# SCH_BSPD_Main.net
KiCad netlist of a schematic drawn in Altium Designer
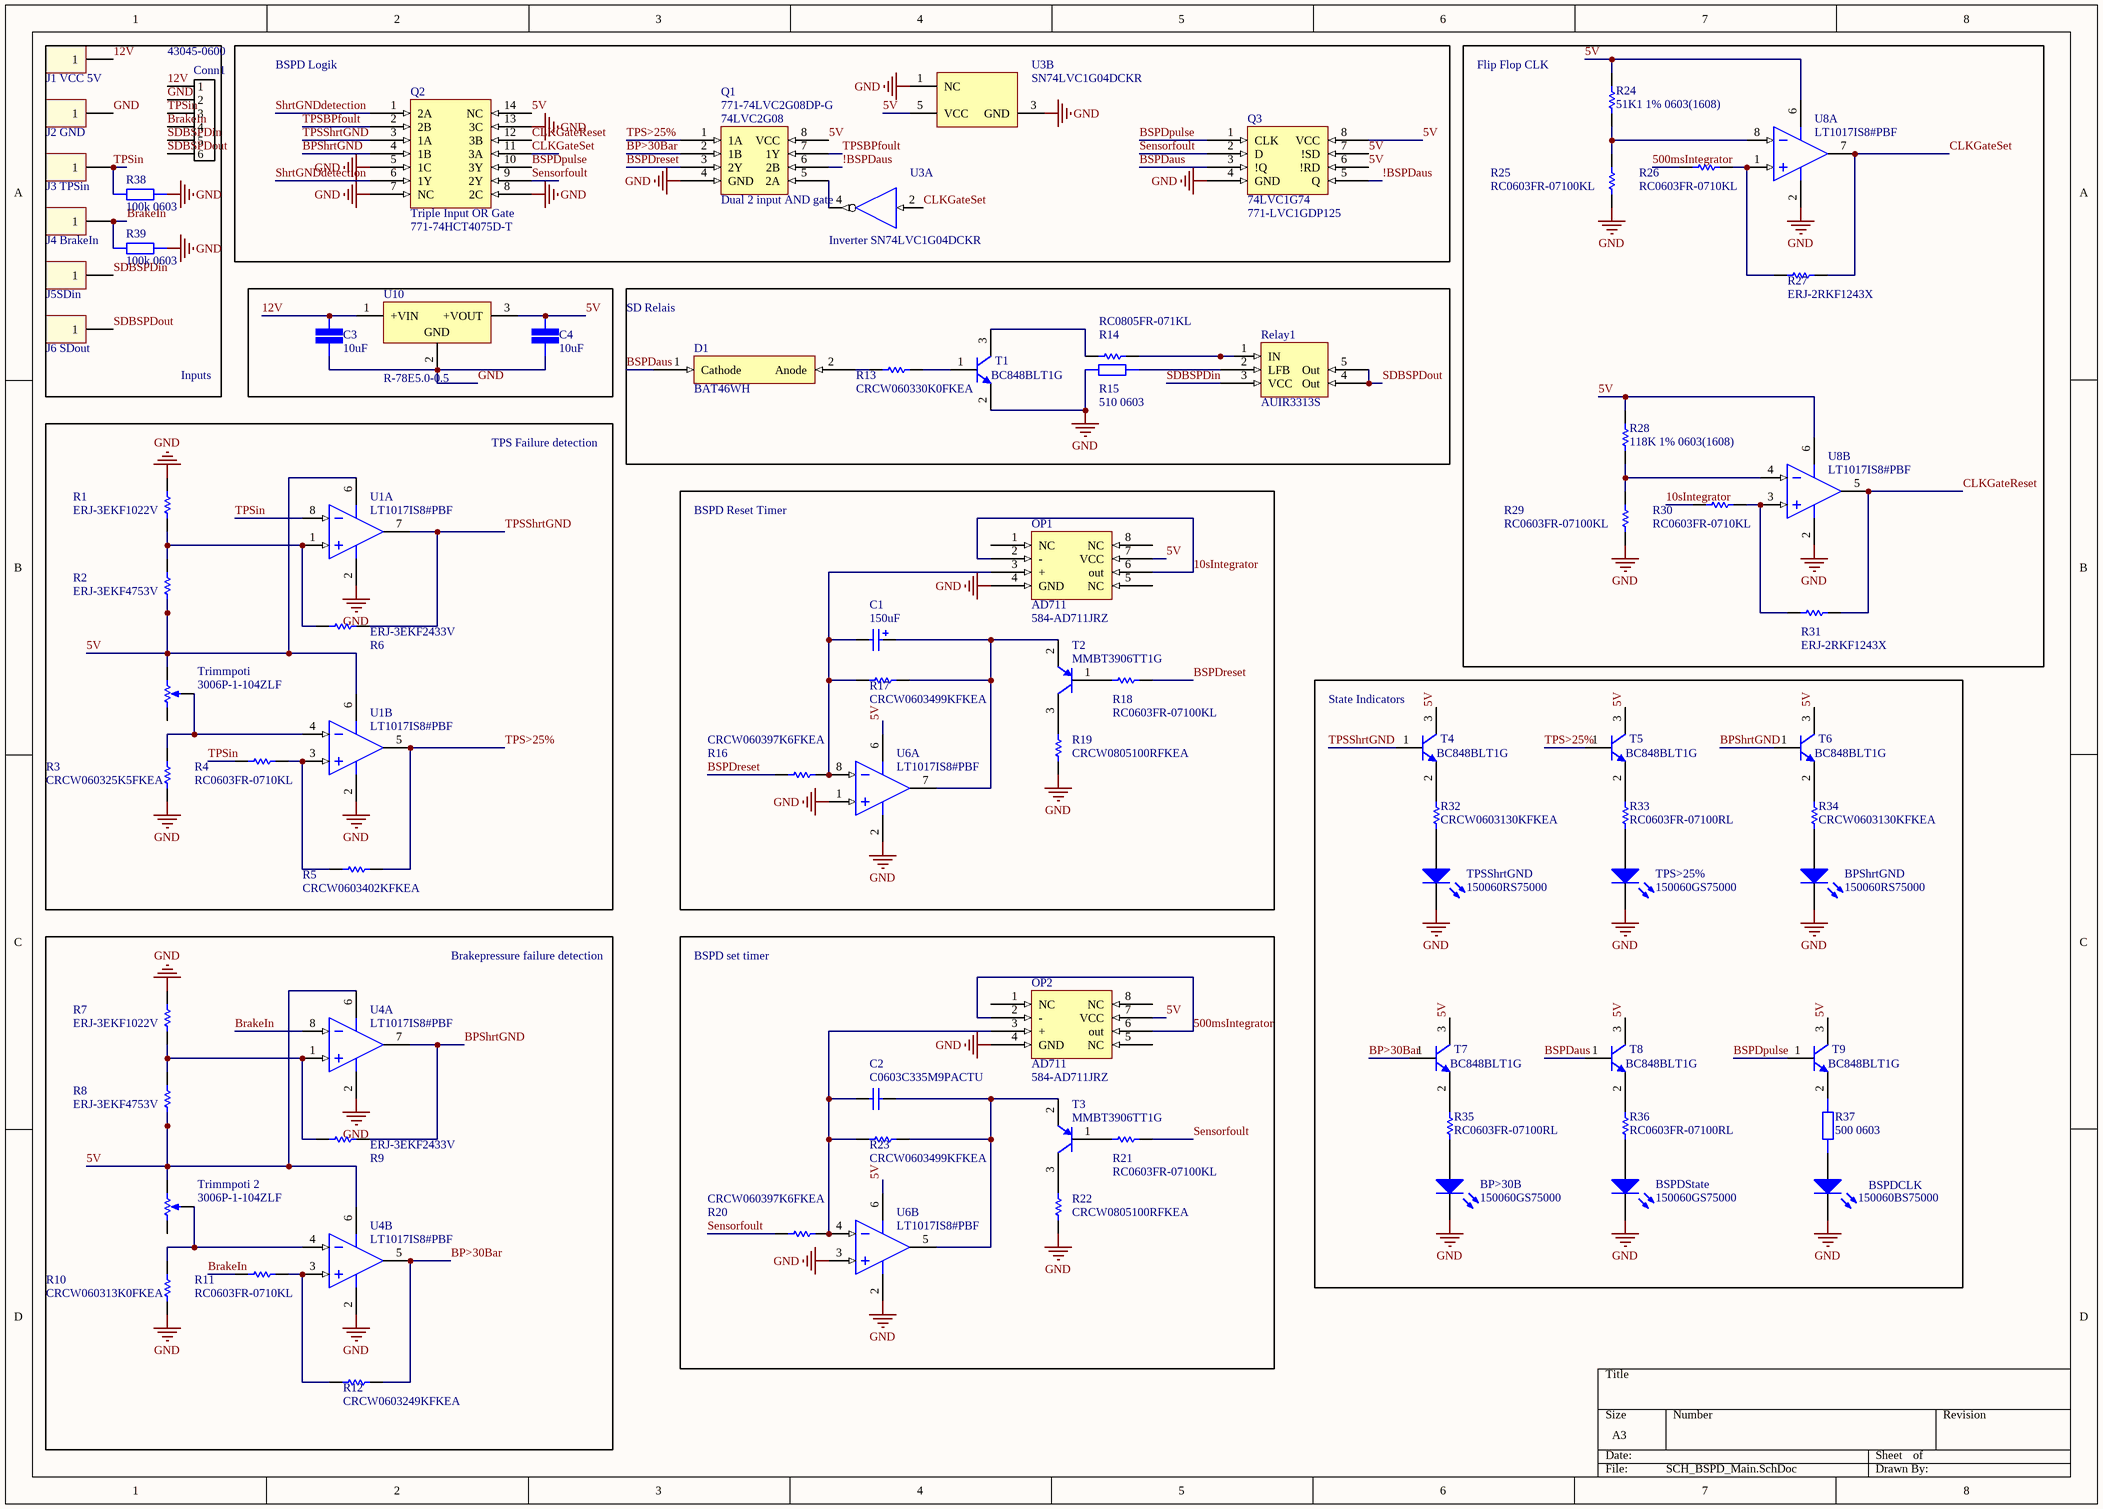
[diagram p0: SCH_BSPD_Main.SchDoc]

(export (version "E")
  (design (tool "Eeschema 10.0.6"))
  (components
    (comp (ref "BP>30B")
      (value "150060GS75000")
      (footprint "0603_A")
      (description "SMD mono-color Chip LED, WL-SMCW, Green")
      (fields (field (name "MANUFACTURER") "Wuerth Elektronik"))
      (libsource (lib "Altium Content Vault") (part "WE-LED_K1A2-2"))
    )
    (comp (ref "BPShrtGND")
      (value "150060RS75000")
      (footprint "0603_A")
      (description "SMD mono-color Chip LED, WL-SMCW, Red")
      (fields (field (name "MANUFACTURER") "Wuerth Elektronik"))
      (libsource (lib "Altium Content Vault") (part "WE-LED_K1A2-2"))
    )
    (comp (ref "BSPDCLK")
      (value "150060BS75000")
      (footprint "0603_A")
      (description "SMD mono-color Chip LED, WL-SMCW, Blue")
      (fields (field (name "MANUFACTURER") "Wuerth Elektronik"))
      (libsource (lib "Altium Content Vault") (part "WE-LED_K1A2-2"))
    )
    (comp (ref "BSPDState")
      (value "150060GS75000")
      (footprint "0603_A")
      (description "SMD mono-color Chip LED, WL-SMCW, Green")
      (fields (field (name "MANUFACTURER") "Wuerth Elektronik"))
      (libsource (lib "Altium Content Vault") (part "WE-LED_K1A2-2"))
    )
    (comp (ref "C1")
      (value "150uF")
      (footprint "WCAP-PSLC_10x12.4")
      (description "WCAP-PSLC Aluminum Polymer Capacitors, size Ф10x12.4mm, 25V DC, 150uF")
      (fields (field (name "PART NUMBER") "875075561006") (field (name "PUBLISHER") "Wurth Elektronik"))
      (libsource (lib "ALTIUM-WCAP-PSLC-rev17b") (part "875075561006"))
    )
    (comp (ref "C2")
      (value "C0603C335M9PACTU")
      (footprint "CAPC1608X90X35NL15T15")
      (fields (field (name "MANUFACTURER") "Kemet"))
      (libsource (lib "Altium Content Vault") (part "CAP"))
    )
    (comp (ref "C3")
      (value "10uF")
      (footprint "CAP 0805/2012")
      (description "Capacitor with multiple Footprints")
      (fields (field (name "Comment") "SMD Capacitor"))
      (libsource (lib "Standardbauteile") (part "SMD Capacitor"))
    )
    (comp (ref "C4")
      (value "10uF")
      (footprint "CAP 0805/2012")
      (description "Capacitor with multiple Footprints")
      (fields (field (name "Comment") "SMD Capacitor"))
      (libsource (lib "Standardbauteile") (part "SMD Capacitor"))
    )
    (comp (ref "Conn1")
      (value "43045-0600")
      (footprint "43045-0600")
      (description "Molex Micro-Fit 3.0 6-Pin\r\n600V\r\n8.5A")
      (libsource (lib "Standardbauteile") (part "MicroFit3.0 6-Pin"))
    )
    (comp (ref "D1")
      (value "BAT46WH")
      (footprint "DIOM2715X18N")
      (libsource (lib "Integrated_LibraryLukas") (part "BAT46WH"))
    )
    (comp (ref "J1 VCC 5V")
      (value "61300111121")
      (footprint "61300111121")
      (description "WR-PHD 2.54 mm THT Pin Header, 1p")
      (fields (field (name "PUBLISHER") "Wurth Elektronik"))
      (libsource (lib "ALTIUM-PHD_2_54_THT_DUAL_PIN_HEADER_6130XX21121") (part "61300111121"))
    )
    (comp (ref "J2 GND")
      (value "61300111121")
      (footprint "61300111121")
      (description "WR-PHD 2.54 mm THT Pin Header, 1p")
      (fields (field (name "PUBLISHER") "Wurth Elektronik"))
      (libsource (lib "ALTIUM-PHD_2_54_THT_DUAL_PIN_HEADER_6130XX21121") (part "61300111121"))
    )
    (comp (ref "J3 TPSin")
      (value "61300111121")
      (footprint "61300111121")
      (description "WR-PHD 2.54 mm THT Pin Header, 1p")
      (fields (field (name "PUBLISHER") "Wurth Elektronik"))
      (libsource (lib "ALTIUM-PHD_2_54_THT_DUAL_PIN_HEADER_6130XX21121") (part "61300111121"))
    )
    (comp (ref "J4 BrakeIn")
      (value "61300111121")
      (footprint "61300111121")
      (description "WR-PHD 2.54 mm THT Pin Header, 1p")
      (fields (field (name "PUBLISHER") "Wurth Elektronik"))
      (libsource (lib "ALTIUM-PHD_2_54_THT_DUAL_PIN_HEADER_6130XX21121") (part "61300111121"))
    )
    (comp (ref "J5SDin")
      (value "61300111121")
      (footprint "61300111121")
      (description "WR-PHD 2.54 mm THT Pin Header, 1p")
      (fields (field (name "PUBLISHER") "Wurth Elektronik"))
      (libsource (lib "ALTIUM-PHD_2_54_THT_DUAL_PIN_HEADER_6130XX21121") (part "61300111121"))
    )
    (comp (ref "J6 SDout")
      (value "61300111121")
      (footprint "61300111121")
      (description "WR-PHD 2.54 mm THT Pin Header, 1p")
      (fields (field (name "PUBLISHER") "Wurth Elektronik"))
      (libsource (lib "ALTIUM-PHD_2_54_THT_DUAL_PIN_HEADER_6130XX21121") (part "61300111121"))
    )
    (comp (ref "OP1")
      (value "AD711")
      (footprint "SOIC8; SOIC127P600X175-8N")
      (fields (field (name "SUPPLIER PART NUMBER 1") "584-AD711JRZ"))
      (libsource (lib "Integrated_LibraryLukas") (part "AD711"))
    )
    (comp (ref "OP2")
      (value "AD711")
      (footprint "SOIC8; SOIC127P600X175-8N")
      (fields (field (name "SUPPLIER PART NUMBER 1") "584-AD711JRZ"))
      (libsource (lib "Integrated_LibraryLukas") (part "AD711"))
    )
    (comp (ref "Q1")
      (value "Dual 2 input AND gate")
      (footprint "TSSOP8; TSOP65P400X110-8N")
      (fields (field (name "SUPPLIER PART NUMBER 1") "771-74LVC2G08DP-G"))
      (libsource (lib "Integrated_LibraryLukas") (part "74LVC2G08-Q100"))
    )
    (comp (ref "Q2")
      (value "Triple Input OR Gate")
      (footprint "SOIC14; SOIC127P600X175-14N")
      (fields (field (name "SUPPLIER PART NUMBER 1") "771-74HCT4075D-T"))
      (libsource (lib "Integrated_LibraryLukas") (part "74HCT4075D,653"))
    )
    (comp (ref "Q3")
      (value "74LVC1G74")
      (footprint "TSSOP8; TSOP65P400X110-8N")
      (fields (field (name "SUPPLIER PART NUMBER 1") "771-LVC1GDP125"))
      (libsource (lib "Integrated_LibraryLukas") (part "74LVC1G74"))
    )
    (comp (ref "R1")
      (value "ERJ-3EKF1022V")
      (footprint "RESC1608X55X30LL15T15")
      (fields (field (name "MANUFACTURER") "Panasonic"))
      (libsource (lib "Altium Content Vault") (part "RES"))
    )
    (comp (ref "R2")
      (value "ERJ-3EKF4753V")
      (footprint "RESC1608X55X30LL15T15")
      (fields (field (name "MANUFACTURER") "Panasonic"))
      (libsource (lib "Altium Content Vault") (part "RES"))
    )
    (comp (ref "R3")
      (value "CRCW060325K5FKEA")
      (footprint "RESC1609X50X30ML10T20")
      (fields (field (name "MANUFACTURER") "Vishay Dale"))
      (libsource (lib "Altium Content Vault") (part "RES"))
    )
    (comp (ref "R4")
      (value "RC0603FR-0710KL")
      (footprint "RESC1608X55X25ML10T15")
      (description "Chip Resistor, 10 KOhm, +/- 1%, 01 W, -55 to 155 degC, 0603 (1608 Metric), RoHS, Tape and Reel")
      (fields (field (name "MANUFACTURER") "Yageo") (field (name "TOLERANCE") "1%"))
      (libsource (lib "Altium Content Vault") (part "RES-2"))
    )
    (comp (ref "R5")
      (value "CRCW0603402KFKEA")
      (footprint "RESC1609X50X30ML10T20")
      (fields (field (name "MANUFACTURER") "Vishay Dale"))
      (libsource (lib "Altium Content Vault") (part "RES"))
    )
    (comp (ref "R6")
      (value "ERJ-3EKF2433V")
      (footprint "RESC1608X55X30ML15T15")
      (fields (field (name "MANUFACTURER") "Panasonic"))
      (libsource (lib "Altium Content Vault") (part "RES"))
    )
    (comp (ref "R7")
      (value "ERJ-3EKF1022V")
      (footprint "RESC1608X55X30LL15T15")
      (fields (field (name "MANUFACTURER") "Panasonic"))
      (libsource (lib "Altium Content Vault") (part "RES"))
    )
    (comp (ref "R8")
      (value "ERJ-3EKF4753V")
      (footprint "RESC1608X55X30LL15T15")
      (fields (field (name "MANUFACTURER") "Panasonic"))
      (libsource (lib "Altium Content Vault") (part "RES"))
    )
    (comp (ref "R9")
      (value "ERJ-3EKF2433V")
      (footprint "RESC1608X55X30ML15T15")
      (fields (field (name "MANUFACTURER") "Panasonic"))
      (libsource (lib "Altium Content Vault") (part "RES"))
    )
    (comp (ref "R10")
      (value "CRCW060313K0FKEA")
      (footprint "RESC1609X50X30NL10T20")
      (fields (field (name "MANUFACTURER") "Vishay Dale"))
      (libsource (lib "Altium Content Vault") (part "RES"))
    )
    (comp (ref "R11")
      (value "RC0603FR-0710KL")
      (footprint "RESC1608X55X25ML10T15")
      (description "Chip Resistor, 10 KOhm, +/- 1%, 01 W, -55 to 155 degC, 0603 (1608 Metric), RoHS, Tape and Reel")
      (fields (field (name "MANUFACTURER") "Yageo") (field (name "TOLERANCE") "1%"))
      (libsource (lib "Altium Content Vault") (part "RES-2"))
    )
    (comp (ref "R12")
      (value "CRCW0603249KFKEA")
      (footprint "RESC1609X50X30NL10T20")
      (fields (field (name "MANUFACTURER") "Vishay Dale"))
      (libsource (lib "Altium Content Vault") (part "RES"))
    )
    (comp (ref "R13")
      (value "CRCW060330K0FKEA")
      (footprint "RESC1609X50X30LL10T20")
      (fields (field (name "MANUFACTURER") "Vishay Dale"))
      (libsource (lib "Altium Content Vault") (part "RES"))
    )
    (comp (ref "R14")
      (value "RC0805FR-071KL")
      (footprint "RESC2013X60X35ML10T20")
      (description "Chip Resistor, 1 KOhm, +/- 1%, 125 mW, -55 to 155 degC, 0805 (2012 Metric), RoHS, Tape and Reel")
      (fields (field (name "TOLERANCE") "1%") (field (name "MANUFACTURER") "Yageo"))
      (libsource (lib "Altium Content Vault") (part "RES-2"))
    )
    (comp (ref "R15")
      (value "510 0603")
      (footprint "STACKPOLE CSR0603")
      (description "Resistor with multiple footprints")
      (fields (field (name "Comment") "SMD Resistor"))
      (libsource (lib "Standardbauteile") (part "SMD Resistor"))
    )
    (comp (ref "R16")
      (value "CRCW060397K6FKEA")
      (footprint "RESC1609X50X30LL10T20")
      (fields (field (name "MANUFACTURER") "Vishay Dale"))
      (libsource (lib "Altium Content Vault") (part "RES"))
    )
    (comp (ref "R17")
      (value "CRCW0603499KFKEA")
      (footprint "RESC1609X50X30NL10T20")
      (fields (field (name "MANUFACTURER") "Vishay Dale"))
      (libsource (lib "Altium Content Vault") (part "RES"))
    )
    (comp (ref "R18")
      (value "RC0603FR-07100KL")
      (footprint "RESC1608X55X25ML10T15")
      (description "Chip Resistor, 100 KOhm, +/- 1%, 0.1 W, -55 to 155 degC, 0603 (1608 Metric), RoHS, Tape and Reel")
      (fields (field (name "MANUFACTURER") "Yageo") (field (name "TOLERANCE") "1%"))
      (libsource (lib "Altium Content Vault") (part "RES-2"))
    )
    (comp (ref "R19")
      (value "CRCW0805100RFKEA")
      (footprint "RESC2013X50X30LL20T20")
      (fields (field (name "MANUFACTURER") "Vishay Dale"))
      (libsource (lib "Altium Content Vault") (part "RES"))
    )
    (comp (ref "R20")
      (value "CRCW060397K6FKEA")
      (footprint "RESC1609X50X30LL10T20")
      (fields (field (name "MANUFACTURER") "Vishay Dale"))
      (libsource (lib "Altium Content Vault") (part "RES"))
    )
    (comp (ref "R21")
      (value "RC0603FR-07100KL")
      (footprint "RESC1608X55X25ML10T15")
      (description "Chip Resistor, 100 KOhm, +/- 1%, 0.1 W, -55 to 155 degC, 0603 (1608 Metric), RoHS, Tape and Reel")
      (fields (field (name "MANUFACTURER") "Yageo") (field (name "TOLERANCE") "1%"))
      (libsource (lib "Altium Content Vault") (part "RES-2"))
    )
    (comp (ref "R22")
      (value "CRCW0805100RFKEA")
      (footprint "RESC2013X50X30LL20T20")
      (fields (field (name "MANUFACTURER") "Vishay Dale"))
      (libsource (lib "Altium Content Vault") (part "RES"))
    )
    (comp (ref "R23")
      (value "CRCW0603499KFKEA")
      (footprint "RESC1609X50X30NL10T20")
      (fields (field (name "MANUFACTURER") "Vishay Dale"))
      (libsource (lib "Altium Content Vault") (part "RES"))
    )
    (comp (ref "R24")
      (value "51K1 1% 0603(1608)")
      (footprint "RESC0603(1608)_L")
      (description "51K1 0.1W 1% 0603 (1608 Metric)  SMD")
      (fields (field (name "TOLERANCE") "1 %") (field (name "POWER") "0.1 W"))
      (libsource (lib "Altium Content Vault") (part "RES"))
    )
    (comp (ref "R25")
      (value "RC0603FR-07100KL")
      (footprint "RESC1608X55X25ML10T15")
      (description "Chip Resistor, 100 KOhm, +/- 1%, 0.1 W, -55 to 155 degC, 0603 (1608 Metric), RoHS, Tape and Reel")
      (fields (field (name "MANUFACTURER") "Yageo") (field (name "TOLERANCE") "1%"))
      (libsource (lib "Altium Content Vault") (part "RES-2"))
    )
    (comp (ref "R26")
      (value "RC0603FR-0710KL")
      (footprint "RESC1608X55X25ML10T15")
      (description "Chip Resistor, 10 KOhm, +/- 1%, 01 W, -55 to 155 degC, 0603 (1608 Metric), RoHS, Tape and Reel")
      (fields (field (name "MANUFACTURER") "Yageo") (field (name "TOLERANCE") "1%"))
      (libsource (lib "Altium Content Vault") (part "RES-2"))
    )
    (comp (ref "R27")
      (value "ERJ-2RKF1243X")
      (footprint "RESC1005X40X25NL05T05")
      (fields (field (name "MANUFACTURER") "Panasonic"))
      (libsource (lib "Altium Content Vault") (part "RES"))
    )
    (comp (ref "R28")
      (value "118K 1% 0603(1608)")
      (footprint "RESC0603(1608)_M")
      (description "118K 0.1W 1% 0603 (1608 Metric)  SMD")
      (fields (field (name "POWER") "0.1 W") (field (name "TOLERANCE") "1 %"))
      (libsource (lib "Altium Content Vault") (part "RES"))
    )
    (comp (ref "R29")
      (value "RC0603FR-07100KL")
      (footprint "RESC1608X55X25ML10T15")
      (description "Chip Resistor, 100 KOhm, +/- 1%, 0.1 W, -55 to 155 degC, 0603 (1608 Metric), RoHS, Tape and Reel")
      (fields (field (name "MANUFACTURER") "Yageo") (field (name "TOLERANCE") "1%"))
      (libsource (lib "Altium Content Vault") (part "RES-2"))
    )
    (comp (ref "R30")
      (value "RC0603FR-0710KL")
      (footprint "RESC1608X55X25ML10T15")
      (description "Chip Resistor, 10 KOhm, +/- 1%, 01 W, -55 to 155 degC, 0603 (1608 Metric), RoHS, Tape and Reel")
      (fields (field (name "MANUFACTURER") "Yageo") (field (name "TOLERANCE") "1%"))
      (libsource (lib "Altium Content Vault") (part "RES-2"))
    )
    (comp (ref "R31")
      (value "ERJ-2RKF1243X")
      (footprint "RESC1005X40X25NL05T05")
      (fields (field (name "MANUFACTURER") "Panasonic"))
      (libsource (lib "Altium Content Vault") (part "RES"))
    )
    (comp (ref "R32")
      (value "CRCW0603130KFKEA")
      (footprint "RESC1609X50X30NL10T20")
      (fields (field (name "MANUFACTURER") "Vishay Dale"))
      (libsource (lib "Altium Content Vault") (part "RES"))
    )
    (comp (ref "R33")
      (value "RC0603FR-07100RL")
      (footprint "RESC1608X55X25ML10T15")
      (description "Chip Resistor, 100 Ohm, +/- 1%, 0.1 W, -55 to 155 degC, 0603 (1608 Metric), RoHS, Tape and Reel")
      (fields (field (name "TOLERANCE") "1%") (field (name "MANUFACTURER") "Yageo"))
      (libsource (lib "Altium Content Vault") (part "RES-2"))
    )
    (comp (ref "R34")
      (value "CRCW0603130KFKEA")
      (footprint "RESC1609X50X30NL10T20")
      (fields (field (name "MANUFACTURER") "Vishay Dale"))
      (libsource (lib "Altium Content Vault") (part "RES"))
    )
    (comp (ref "R35")
      (value "RC0603FR-07100RL")
      (footprint "RESC1608X55X25ML10T15")
      (description "Chip Resistor, 100 Ohm, +/- 1%, 0.1 W, -55 to 155 degC, 0603 (1608 Metric), RoHS, Tape and Reel")
      (fields (field (name "TOLERANCE") "1%") (field (name "MANUFACTURER") "Yageo"))
      (libsource (lib "Altium Content Vault") (part "RES-2"))
    )
    (comp (ref "R36")
      (value "RC0603FR-07100RL")
      (footprint "RESC1608X55X25ML10T15")
      (description "Chip Resistor, 100 Ohm, +/- 1%, 0.1 W, -55 to 155 degC, 0603 (1608 Metric), RoHS, Tape and Reel")
      (fields (field (name "TOLERANCE") "1%") (field (name "MANUFACTURER") "Yageo"))
      (libsource (lib "Altium Content Vault") (part "RES-2"))
    )
    (comp (ref "R37")
      (value "500 0603")
      (footprint "STACKPOLE CSR0603")
      (description "Resistor with multiple footprints")
      (fields (field (name "Comment") "SMD Resistor"))
      (libsource (lib "Standardbauteile") (part "SMD Resistor"))
    )
    (comp (ref "R38")
      (value "100k 0603")
      (footprint "STACKPOLE CSR0603")
      (description "Resistor with multiple footprints")
      (fields (field (name "Comment") "SMD Resistor"))
      (libsource (lib "Standardbauteile") (part "SMD Resistor"))
    )
    (comp (ref "R39")
      (value "100k 0603")
      (footprint "STACKPOLE CSR0603")
      (description "Resistor with multiple footprints")
      (fields (field (name "Comment") "SMD Resistor"))
      (libsource (lib "Standardbauteile") (part "SMD Resistor"))
    )
    (comp (ref "Relay1")
      (value "AUIR3313S")
      (footprint "D2PAK5 ;DPAK228P1524X483-5N")
      (libsource (lib "Integrated_LibraryLukas") (part "AUIR3313S"))
    )
    (comp (ref "T1")
      (value "BC848BLT1G")
      (footprint "ONSC-SOT-23-3-318-08_V")
      (description "General Purpose Transistor, NPN Silicon, 3-Pin SOT-23, Pb-Free, Tape and Reel")
      (fields (field (name "MANUFACTURER") "On Semiconductor"))
      (libsource (lib "Altium Content Vault") (part "ONSC-NPN-B1E2C3-3"))
    )
    (comp (ref "T2")
      (value "MMBT3906TT1G")
      (footprint "ONSC-SC-75-3-463-01_V")
      (description "General Purpose Transistor, PNP Silicon, 3-Pin SC-75, Pb-Free, Tape and Reel")
      (fields (field (name "MANUFACTURER") "On Semiconductor"))
      (libsource (lib "Altium Content Vault") (part "ONSC-PNP-B1E2C3-3"))
    )
    (comp (ref "T3")
      (value "MMBT3906TT1G")
      (footprint "ONSC-SC-75-3-463-01_V")
      (description "General Purpose Transistor, PNP Silicon, 3-Pin SC-75, Pb-Free, Tape and Reel")
      (fields (field (name "MANUFACTURER") "On Semiconductor"))
      (libsource (lib "Altium Content Vault") (part "ONSC-PNP-B1E2C3-3"))
    )
    (comp (ref "T4")
      (value "BC848BLT1G")
      (footprint "ONSC-SOT-23-3-318-08_V")
      (description "General Purpose Transistor, NPN Silicon, 3-Pin SOT-23, Pb-Free, Tape and Reel")
      (fields (field (name "MANUFACTURER") "On Semiconductor"))
      (libsource (lib "Altium Content Vault") (part "ONSC-NPN-B1E2C3-3"))
    )
    (comp (ref "T5")
      (value "BC848BLT1G")
      (footprint "ONSC-SOT-23-3-318-08_V")
      (description "General Purpose Transistor, NPN Silicon, 3-Pin SOT-23, Pb-Free, Tape and Reel")
      (fields (field (name "MANUFACTURER") "On Semiconductor"))
      (libsource (lib "Altium Content Vault") (part "ONSC-NPN-B1E2C3-3"))
    )
    (comp (ref "T6")
      (value "BC848BLT1G")
      (footprint "ONSC-SOT-23-3-318-08_V")
      (description "General Purpose Transistor, NPN Silicon, 3-Pin SOT-23, Pb-Free, Tape and Reel")
      (fields (field (name "MANUFACTURER") "On Semiconductor"))
      (libsource (lib "Altium Content Vault") (part "ONSC-NPN-B1E2C3-3"))
    )
    (comp (ref "T7")
      (value "BC848BLT1G")
      (footprint "ONSC-SOT-23-3-318-08_V")
      (description "General Purpose Transistor, NPN Silicon, 3-Pin SOT-23, Pb-Free, Tape and Reel")
      (fields (field (name "MANUFACTURER") "On Semiconductor"))
      (libsource (lib "Altium Content Vault") (part "ONSC-NPN-B1E2C3-3"))
    )
    (comp (ref "T8")
      (value "BC848BLT1G")
      (footprint "ONSC-SOT-23-3-318-08_V")
      (description "General Purpose Transistor, NPN Silicon, 3-Pin SOT-23, Pb-Free, Tape and Reel")
      (fields (field (name "MANUFACTURER") "On Semiconductor"))
      (libsource (lib "Altium Content Vault") (part "ONSC-NPN-B1E2C3-3"))
    )
    (comp (ref "T9")
      (value "BC848BLT1G")
      (footprint "ONSC-SOT-23-3-318-08_V")
      (description "General Purpose Transistor, NPN Silicon, 3-Pin SOT-23, Pb-Free, Tape and Reel")
      (fields (field (name "MANUFACTURER") "On Semiconductor"))
      (libsource (lib "Altium Content Vault") (part "ONSC-NPN-B1E2C3-3"))
    )
    (comp (ref "TPS>25%")
      (value "150060GS75000")
      (footprint "0603_A")
      (description "SMD mono-color Chip LED, WL-SMCW, Green")
      (fields (field (name "MANUFACTURER") "Wuerth Elektronik"))
      (libsource (lib "Altium Content Vault") (part "WE-LED_K1A2-2"))
    )
    (comp (ref "TPSShrtGND")
      (value "150060RS75000")
      (footprint "0603_A")
      (description "SMD mono-color Chip LED, WL-SMCW, Red")
      (fields (field (name "MANUFACTURER") "Wuerth Elektronik"))
      (libsource (lib "Altium Content Vault") (part "WE-LED_K1A2-2"))
    )
    (comp (ref "Trimmpoti")
      (value "3006P-1-104ZLF")
      (footprint "BOUR-3006P-3_V")
      (description "Trimming Potentiometer, 100K Ohm +/- 10%, -55 to 125 degC, 3-Pin 19.05 x 4.83 x 6.6 mm THD, RoHS")
      (fields (field (name "MANUFACTURER") "Bourns"))
      (libsource (lib "Altium Content Vault") (part "BOUR-3006P-3"))
    )
    (comp (ref "Trimmpoti 2")
      (value "3006P-1-104ZLF")
      (footprint "BOUR-3006P-3_V")
      (description "Trimming Potentiometer, 100K Ohm +/- 10%, -55 to 125 degC, 3-Pin 19.05 x 4.83 x 6.6 mm THD, RoHS")
      (fields (field (name "MANUFACTURER") "Bourns"))
      (libsource (lib "Altium Content Vault") (part "BOUR-3006P-3"))
    )
    (comp (ref "U1")
      (value "LT1017IS8#PBF")
      (footprint "LT-S8_N")
      (description "Micropower Comparator, 2 Channels, 1.2 to 40 V, -40 to +85 degC, 8-pin SOP (S8)")
      (fields (field (name "MANUFACTURER") "Linear Technology") (field (name "GENERIC PART NUMBER") "LT1017"))
      (libsource (lib "Altium Content Vault") (part "LT-LT1017-SO8"))
    )
    (comp (ref "U3")
      (value "Inverter SN74LVC1G04DCKR")
      (footprint "DCK0005A_N")
      (description "Single Inverter, DCK0005A, LARGE T&R")
      (fields
        (field (name "GENERIC PART NUMBER") "SN74LVC1G04")
        (field (name "MANUFACTURER") "Texas Instruments")
      )
      (libsource (lib "Altium Content Vault") (part "TI-SN74XXX1XX4-XX-5"))
    )
    (comp (ref "U4")
      (value "LT1017IS8#PBF")
      (footprint "LT-S8_N")
      (description "Micropower Comparator, 2 Channels, 1.2 to 40 V, -40 to +85 degC, 8-pin SOP (S8)")
      (fields (field (name "MANUFACTURER") "Linear Technology") (field (name "GENERIC PART NUMBER") "LT1017"))
      (libsource (lib "Altium Content Vault") (part "LT-LT1017-SO8"))
    )
    (comp (ref "U6")
      (value "LT1017IS8#PBF")
      (footprint "LT-S8_N")
      (description "Micropower Comparator, 2 Channels, 1.2 to 40 V, -40 to +85 degC, 8-pin SOP (S8)")
      (fields (field (name "MANUFACTURER") "Linear Technology") (field (name "GENERIC PART NUMBER") "LT1017"))
      (libsource (lib "Altium Content Vault") (part "LT-LT1017-SO8"))
    )
    (comp (ref "U8")
      (value "LT1017IS8#PBF")
      (footprint "LT-S8_N")
      (description "Micropower Comparator, 2 Channels, 1.2 to 40 V, -40 to +85 degC, 8-pin SOP (S8)")
      (fields (field (name "MANUFACTURER") "Linear Technology") (field (name "GENERIC PART NUMBER") "LT1017"))
      (libsource (lib "Altium Content Vault") (part "LT-LT1017-SO8"))
    )
    (comp (ref "U10")
      (value "R-78E5.0-0.5")
      (footprint "REPO-R-78E-0.5-3_V")
      (description "DC/DC-Converter, 5 V Single Output, 500 mA, -40 to 85 degC, 3-Pin THD, RoHS, Tube")
      (fields (field (name "MANUFACTURER") "Recom Power"))
      (libsource (lib "Altium Content Vault") (part "REPO-R-78XX-3"))
    )
  )
  (nets
    (net (code "1") (name "/!BSPDaus") (class "Default")
      (node (ref "Q1") (pin "6") (pinfunction "2B_6") (pintype "input"))
      (node (ref "Q3") (pin "5") (pinfunction "Q_5") (pintype "input"))
    )
    (net (code "2") (name "/5V") (class "Default")
      (node (ref "C4") (pin "2") (pinfunction "2_2") (pintype "passive"))
      (node (ref "OP1") (pin "7") (pinfunction "VCC_7") (pintype "input"))
      (node (ref "OP2") (pin "7") (pinfunction "VCC_7") (pintype "input"))
      (node (ref "Q1") (pin "8") (pinfunction "VCC_8") (pintype "input"))
      (node (ref "Q2") (pin "14") (pinfunction "NC_14") (pintype "input"))
      (node (ref "Q3") (pin "6") (pinfunction "!RD_6") (pintype "input"))
      (node (ref "Q3") (pin "7") (pinfunction "!SD_7") (pintype "input"))
      (node (ref "Q3") (pin "8") (pinfunction "VCC_8") (pintype "input"))
      (node (ref "R2") (pin "1") (pinfunction "1_1") (pintype "passive"))
      (node (ref "R24") (pin "2") (pinfunction "2_2") (pintype "passive"))
      (node (ref "R28") (pin "2") (pinfunction "2_2") (pintype "passive"))
      (node (ref "R8") (pin "1") (pinfunction "1_1") (pintype "passive"))
      (node (ref "T4") (pin "3") (pinfunction "C_3") (pintype "passive"))
      (node (ref "T5") (pin "3") (pinfunction "C_3") (pintype "passive"))
      (node (ref "T6") (pin "3") (pinfunction "C_3") (pintype "passive"))
      (node (ref "T7") (pin "3") (pinfunction "C_3") (pintype "passive"))
      (node (ref "T8") (pin "3") (pinfunction "C_3") (pintype "passive"))
      (node (ref "T9") (pin "3") (pinfunction "C_3") (pintype "passive"))
      (node (ref "Trimmpoti") (pin "1") (pinfunction "CCW_1") (pintype "passive"))
      (node (ref "Trimmpoti 2") (pin "1") (pinfunction "CCW_1") (pintype "passive"))
      (node (ref "U1") (pin "6") (pinfunction "V+_6") (pintype "power_in"))
      (node (ref "U10") (pin "3") (pinfunction "+VOUT_3") (pintype "power_in"))
      (node (ref "U3") (pin "5") (pinfunction "VCC_5") (pintype "power_in"))
      (node (ref "U4") (pin "6") (pinfunction "V+_6") (pintype "power_in"))
      (node (ref "U6") (pin "6") (pinfunction "V+_6") (pintype "power_in"))
      (node (ref "U8") (pin "6") (pinfunction "V+_6") (pintype "power_in"))
    )
    (net (code "3") (name "/10sIntegrator") (class "Default")
      (node (ref "OP1") (pin "2") (pinfunction "-_2") (pintype "input"))
      (node (ref "OP1") (pin "6") (pinfunction "out_6") (pintype "input"))
      (node (ref "R30") (pin "1") (pinfunction "1_1") (pintype "passive"))
    )
    (net (code "4") (name "/12V") (class "Default")
      (node (ref "C3") (pin "2") (pinfunction "2_2") (pintype "passive"))
      (node (ref "Conn1") (pin "1") (pinfunction "1_1") (pintype "passive"))
      (node (ref "J1 VCC 5V") (pin "1") (pinfunction "1_1") (pintype "passive"))
      (node (ref "U10") (pin "1") (pinfunction "+VIN_1") (pintype "power_in"))
    )
    (net (code "5") (name "/500msIntegrator") (class "Default")
      (node (ref "OP2") (pin "2") (pinfunction "-_2") (pintype "input"))
      (node (ref "OP2") (pin "6") (pinfunction "out_6") (pintype "input"))
      (node (ref "R26") (pin "1") (pinfunction "1_1") (pintype "passive"))
    )
    (net (code "6") (name "/BP>30Bar") (class "Default")
      (node (ref "Q1") (pin "2") (pinfunction "1B_2") (pintype "input"))
      (node (ref "R12") (pin "2") (pinfunction "2_2") (pintype "passive"))
      (node (ref "T7") (pin "1") (pinfunction "B_1") (pintype "passive"))
      (node (ref "U4") (pin "5") (pinfunction "OUT_B_5") (pintype "open_collector"))
    )
    (net (code "7") (name "/BPShrtGND") (class "Default")
      (node (ref "Q2") (pin "4") (pinfunction "1B_4") (pintype "input"))
      (node (ref "R9") (pin "2") (pinfunction "2_2") (pintype "passive"))
      (node (ref "T6") (pin "1") (pinfunction "B_1") (pintype "passive"))
      (node (ref "U4") (pin "7") (pinfunction "OUT_A_7") (pintype "open_collector"))
    )
    (net (code "8") (name "/BSPDaus") (class "Default")
      (node (ref "D1") (pin "1") (pinfunction "Cathode_1") (pintype "input"))
      (node (ref "Q3") (pin "3") (pinfunction "!Q_3") (pintype "input"))
      (node (ref "T8") (pin "1") (pinfunction "B_1") (pintype "passive"))
    )
    (net (code "9") (name "/BSPDpulse") (class "Default")
      (node (ref "Q2") (pin "10") (pinfunction "3Y_10") (pintype "input"))
      (node (ref "Q3") (pin "1") (pinfunction "CLK_1") (pintype "input"))
      (node (ref "T9") (pin "1") (pinfunction "B_1") (pintype "passive"))
    )
    (net (code "10") (name "/BSPDreset") (class "Default")
      (node (ref "Q1") (pin "3") (pinfunction "2Y_3") (pintype "input"))
      (node (ref "R16") (pin "1") (pinfunction "1_1") (pintype "passive"))
      (node (ref "R18") (pin "1") (pinfunction "1_1") (pintype "passive"))
    )
    (net (code "11") (name "/BrakeIn") (class "Default")
      (node (ref "Conn1") (pin "4") (pinfunction "4_4") (pintype "passive"))
      (node (ref "J4 BrakeIn") (pin "1") (pinfunction "1_1") (pintype "passive"))
      (node (ref "R11") (pin "1") (pinfunction "1_1") (pintype "passive"))
      (node (ref "R39") (pin "1") (pinfunction "1_1") (pintype "passive"))
      (node (ref "U4") (pin "8") (pinfunction "-IN_A_8") (pintype "input"))
    )
    (net (code "12") (name "/CLKGateReset") (class "Default")
      (node (ref "Q2") (pin "12") (pinfunction "3B_12") (pintype "input"))
      (node (ref "R31") (pin "2") (pinfunction "2_2") (pintype "passive"))
      (node (ref "U8") (pin "5") (pinfunction "OUT_B_5") (pintype "open_collector"))
    )
    (net (code "13") (name "/CLKGateSet") (class "Default")
      (node (ref "Q2") (pin "11") (pinfunction "3A_11") (pintype "input"))
      (node (ref "R27") (pin "2") (pinfunction "2_2") (pintype "passive"))
      (node (ref "U3") (pin "2") (pinfunction "A_2") (pintype "input"))
      (node (ref "U8") (pin "7") (pinfunction "OUT_A_7") (pintype "open_collector"))
    )
    (net (code "14") (name "/SDBSPDin") (class "Default")
      (node (ref "Conn1") (pin "5") (pinfunction "5_5") (pintype "passive"))
      (node (ref "J5SDin") (pin "1") (pinfunction "1_1") (pintype "passive"))
      (node (ref "Relay1") (pin "3") (pinfunction "VCC_3") (pintype "input"))
    )
    (net (code "15") (name "/SDBSPDout") (class "Default")
      (node (ref "Conn1") (pin "6") (pinfunction "6_6") (pintype "passive"))
      (node (ref "J6 SDout") (pin "1") (pinfunction "1_1") (pintype "passive"))
      (node (ref "Relay1") (pin "4") (pinfunction "Out_4") (pintype "input"))
      (node (ref "Relay1") (pin "5") (pinfunction "Out_5") (pintype "input"))
    )
    (net (code "16") (name "/Sensorfoult") (class "Default")
      (node (ref "Q2") (pin "9") (pinfunction "2Y_9") (pintype "input"))
      (node (ref "Q3") (pin "2") (pinfunction "D_2") (pintype "input"))
      (node (ref "R20") (pin "1") (pinfunction "1_1") (pintype "passive"))
      (node (ref "R21") (pin "1") (pinfunction "1_1") (pintype "passive"))
    )
    (net (code "17") (name "/ShrtGNDdetection") (class "Default")
      (node (ref "Q2") (pin "1") (pinfunction "2A_1") (pintype "input"))
      (node (ref "Q2") (pin "6") (pinfunction "1Y_6") (pintype "input"))
    )
    (net (code "18") (name "/TPS>25%") (class "Default")
      (node (ref "Q1") (pin "1") (pinfunction "1A_1") (pintype "input"))
      (node (ref "R5") (pin "2") (pinfunction "2_2") (pintype "passive"))
      (node (ref "T5") (pin "1") (pinfunction "B_1") (pintype "passive"))
      (node (ref "U1") (pin "5") (pinfunction "OUT_B_5") (pintype "open_collector"))
    )
    (net (code "19") (name "/TPSBPfoult") (class "Default")
      (node (ref "Q1") (pin "7") (pinfunction "1Y_7") (pintype "input"))
      (node (ref "Q2") (pin "2") (pinfunction "2B_2") (pintype "input"))
    )
    (net (code "20") (name "/TPSShrtGND") (class "Default")
      (node (ref "Q2") (pin "3") (pinfunction "1A_3") (pintype "input"))
      (node (ref "R6") (pin "2") (pinfunction "2_2") (pintype "passive"))
      (node (ref "T4") (pin "1") (pinfunction "B_1") (pintype "passive"))
      (node (ref "U1") (pin "7") (pinfunction "OUT_A_7") (pintype "open_collector"))
    )
    (net (code "21") (name "/TPSin") (class "Default")
      (node (ref "Conn1") (pin "3") (pinfunction "3_3") (pintype "passive"))
      (node (ref "J3 TPSin") (pin "1") (pinfunction "1_1") (pintype "passive"))
      (node (ref "R38") (pin "1") (pinfunction "1_1") (pintype "passive"))
      (node (ref "R4") (pin "1") (pinfunction "1_1") (pintype "passive"))
      (node (ref "U1") (pin "8") (pinfunction "-IN_A_8") (pintype "input"))
    )
    (net (code "22") (name "GND") (class "Default")
      (node (ref "BP>30B") (pin "1") (pinfunction "K_1") (pintype "passive"))
      (node (ref "BPShrtGND") (pin "1") (pinfunction "K_1") (pintype "passive"))
      (node (ref "BSPDCLK") (pin "1") (pinfunction "K_1") (pintype "passive"))
      (node (ref "BSPDState") (pin "1") (pinfunction "K_1") (pintype "passive"))
      (node (ref "C3") (pin "1") (pinfunction "1_1") (pintype "passive"))
      (node (ref "C4") (pin "1") (pinfunction "1_1") (pintype "passive"))
      (node (ref "Conn1") (pin "2") (pinfunction "2_2") (pintype "passive"))
      (node (ref "J2 GND") (pin "1") (pinfunction "1_1") (pintype "passive"))
      (node (ref "OP1") (pin "4") (pinfunction "GND_4") (pintype "input"))
      (node (ref "OP2") (pin "4") (pinfunction "GND_4") (pintype "input"))
      (node (ref "Q1") (pin "4") (pinfunction "GND_4") (pintype "input"))
      (node (ref "Q2") (pin "13") (pinfunction "3C_13") (pintype "input"))
      (node (ref "Q2") (pin "5") (pinfunction "1C_5") (pintype "input"))
      (node (ref "Q2") (pin "7") (pinfunction "NC_7") (pintype "input"))
      (node (ref "Q2") (pin "8") (pinfunction "2C_8") (pintype "input"))
      (node (ref "Q3") (pin "4") (pinfunction "GND_4") (pintype "input"))
      (node (ref "R1") (pin "2") (pinfunction "2_2") (pintype "passive"))
      (node (ref "R10") (pin "1") (pinfunction "1_1") (pintype "passive"))
      (node (ref "R15") (pin "1") (pinfunction "1_1") (pintype "passive"))
      (node (ref "R19") (pin "2") (pinfunction "2_2") (pintype "passive"))
      (node (ref "R22") (pin "2") (pinfunction "2_2") (pintype "passive"))
      (node (ref "R25") (pin "1") (pinfunction "1_1") (pintype "passive"))
      (node (ref "R29") (pin "1") (pinfunction "1_1") (pintype "passive"))
      (node (ref "R3") (pin "1") (pinfunction "1_1") (pintype "passive"))
      (node (ref "R38") (pin "2") (pinfunction "2_2") (pintype "passive"))
      (node (ref "R39") (pin "2") (pinfunction "2_2") (pintype "passive"))
      (node (ref "R7") (pin "2") (pinfunction "2_2") (pintype "passive"))
      (node (ref "T1") (pin "2") (pinfunction "E_2") (pintype "passive"))
      (node (ref "TPS>25%") (pin "1") (pinfunction "K_1") (pintype "passive"))
      (node (ref "TPSShrtGND") (pin "1") (pinfunction "K_1") (pintype "passive"))
      (node (ref "U1") (pin "2") (pinfunction "V-_2") (pintype "power_in"))
      (node (ref "U10") (pin "2") (pinfunction "GND_2") (pintype "power_in"))
      (node (ref "U3") (pin "1") (pinfunction "NC_1") (pintype "passive"))
      (node (ref "U3") (pin "3") (pinfunction "GND_3") (pintype "power_in"))
      (node (ref "U4") (pin "2") (pinfunction "V-_2") (pintype "power_in"))
      (node (ref "U6") (pin "1") (pinfunction "+IN_A_1") (pintype "input"))
      (node (ref "U6") (pin "2") (pinfunction "V-_2") (pintype "power_in"))
      (node (ref "U6") (pin "3") (pinfunction "+IN_B_3") (pintype "input"))
      (node (ref "U8") (pin "2") (pinfunction "V-_2") (pintype "power_in"))
    )
    (net (code "23") (name "Net-(BP>30B-A)") (class "Default")
      (node (ref "BP>30B") (pin "2") (pinfunction "A_2") (pintype "passive"))
      (node (ref "R35") (pin "2") (pinfunction "2_2") (pintype "passive"))
    )
    (net (code "24") (name "Net-(BPShrtGND-A)") (class "Default")
      (node (ref "BPShrtGND") (pin "2") (pinfunction "A_2") (pintype "passive"))
      (node (ref "R34") (pin "1") (pinfunction "1_1") (pintype "passive"))
    )
    (net (code "25") (name "Net-(BSPDCLK-A)") (class "Default")
      (node (ref "BSPDCLK") (pin "2") (pinfunction "A_2") (pintype "passive"))
      (node (ref "R37") (pin "1") (pinfunction "1_1") (pintype "passive"))
    )
    (net (code "26") (name "Net-(BSPDState-A)") (class "Default")
      (node (ref "BSPDState") (pin "2") (pinfunction "A_2") (pintype "passive"))
      (node (ref "R36") (pin "2") (pinfunction "2_2") (pintype "passive"))
    )
    (net (code "27") (name "Net-(C1-N)") (class "Default")
      (node (ref "C1") (pin "2") (pinfunction "N_2") (pintype "passive"))
      (node (ref "OP1") (pin "3") (pinfunction "+_3") (pintype "input"))
      (node (ref "R16") (pin "2") (pinfunction "2_2") (pintype "passive"))
      (node (ref "R17") (pin "1") (pinfunction "1_1") (pintype "passive"))
      (node (ref "U6") (pin "8") (pinfunction "-IN_A_8") (pintype "input"))
    )
    (net (code "28") (name "Net-(C1-P)") (class "Default")
      (node (ref "C1") (pin "1") (pinfunction "P_1") (pintype "passive"))
      (node (ref "R17") (pin "2") (pinfunction "2_2") (pintype "passive"))
      (node (ref "T2") (pin "2") (pinfunction "E_2") (pintype "passive"))
      (node (ref "U6") (pin "7") (pinfunction "OUT_A_7") (pintype "open_collector"))
    )
    (net (code "29") (name "Net-(D1-Anode)") (class "Default")
      (node (ref "D1") (pin "2") (pinfunction "Anode_2") (pintype "input"))
      (node (ref "R13") (pin "1") (pinfunction "1_1") (pintype "passive"))
    )
    (net (code "30") (name "Net-(OP2-+)") (class "Default")
      (node (ref "C2") (pin "1") (pinfunction "1_1") (pintype "passive"))
      (node (ref "OP2") (pin "3") (pinfunction "+_3") (pintype "input"))
      (node (ref "R20") (pin "2") (pinfunction "2_2") (pintype "passive"))
      (node (ref "R23") (pin "1") (pinfunction "1_1") (pintype "passive"))
      (node (ref "U6") (pin "4") (pinfunction "-IN_B_4") (pintype "input"))
    )
    (net (code "31") (name "Net-(Q1-2A)") (class "Default")
      (node (ref "Q1") (pin "5") (pinfunction "2A_5") (pintype "input"))
      (node (ref "U3") (pin "4") (pinfunction "Y_4") (pintype "output"))
    )
    (net (code "32") (name "Net-(Relay1-IN)") (class "Default")
      (node (ref "R14") (pin "2") (pinfunction "2_2") (pintype "passive"))
      (node (ref "Relay1") (pin "1") (pinfunction "IN_1") (pintype "input"))
    )
    (net (code "33") (name "Net-(Relay1-LFB)") (class "Default")
      (node (ref "R15") (pin "2") (pinfunction "2_2") (pintype "passive"))
      (node (ref "Relay1") (pin "2") (pinfunction "LFB_2") (pintype "input"))
    )
    (net (code "34") (name "Net-(T1-B)") (class "Default")
      (node (ref "R13") (pin "2") (pinfunction "2_2") (pintype "passive"))
      (node (ref "T1") (pin "1") (pinfunction "B_1") (pintype "passive"))
    )
    (net (code "35") (name "Net-(T1-C)") (class "Default")
      (node (ref "R14") (pin "1") (pinfunction "1_1") (pintype "passive"))
      (node (ref "T1") (pin "3") (pinfunction "C_3") (pintype "passive"))
    )
    (net (code "36") (name "Net-(T2-B)") (class "Default")
      (node (ref "R18") (pin "2") (pinfunction "2_2") (pintype "passive"))
      (node (ref "T2") (pin "1") (pinfunction "B_1") (pintype "passive"))
    )
    (net (code "37") (name "Net-(T2-C)") (class "Default")
      (node (ref "R19") (pin "1") (pinfunction "1_1") (pintype "passive"))
      (node (ref "T2") (pin "3") (pinfunction "C_3") (pintype "passive"))
    )
    (net (code "38") (name "Net-(T3-B)") (class "Default")
      (node (ref "R21") (pin "2") (pinfunction "2_2") (pintype "passive"))
      (node (ref "T3") (pin "1") (pinfunction "B_1") (pintype "passive"))
    )
    (net (code "39") (name "Net-(T3-C)") (class "Default")
      (node (ref "R22") (pin "1") (pinfunction "1_1") (pintype "passive"))
      (node (ref "T3") (pin "3") (pinfunction "C_3") (pintype "passive"))
    )
    (net (code "40") (name "Net-(T3-E)") (class "Default")
      (node (ref "C2") (pin "2") (pinfunction "2_2") (pintype "passive"))
      (node (ref "R23") (pin "2") (pinfunction "2_2") (pintype "passive"))
      (node (ref "T3") (pin "2") (pinfunction "E_2") (pintype "passive"))
      (node (ref "U6") (pin "5") (pinfunction "OUT_B_5") (pintype "open_collector"))
    )
    (net (code "41") (name "Net-(T4-E)") (class "Default")
      (node (ref "R32") (pin "2") (pinfunction "2_2") (pintype "passive"))
      (node (ref "T4") (pin "2") (pinfunction "E_2") (pintype "passive"))
    )
    (net (code "42") (name "Net-(T5-E)") (class "Default")
      (node (ref "R33") (pin "1") (pinfunction "1_1") (pintype "passive"))
      (node (ref "T5") (pin "2") (pinfunction "E_2") (pintype "passive"))
    )
    (net (code "43") (name "Net-(T6-E)") (class "Default")
      (node (ref "R34") (pin "2") (pinfunction "2_2") (pintype "passive"))
      (node (ref "T6") (pin "2") (pinfunction "E_2") (pintype "passive"))
    )
    (net (code "44") (name "Net-(T7-E)") (class "Default")
      (node (ref "R35") (pin "1") (pinfunction "1_1") (pintype "passive"))
      (node (ref "T7") (pin "2") (pinfunction "E_2") (pintype "passive"))
    )
    (net (code "45") (name "Net-(T8-E)") (class "Default")
      (node (ref "R36") (pin "1") (pinfunction "1_1") (pintype "passive"))
      (node (ref "T8") (pin "2") (pinfunction "E_2") (pintype "passive"))
    )
    (net (code "46") (name "Net-(T9-E)") (class "Default")
      (node (ref "R37") (pin "2") (pinfunction "2_2") (pintype "passive"))
      (node (ref "T9") (pin "2") (pinfunction "E_2") (pintype "passive"))
    )
    (net (code "47") (name "Net-(TPS>25%-A)") (class "Default")
      (node (ref "R33") (pin "2") (pinfunction "2_2") (pintype "passive"))
      (node (ref "TPS>25%") (pin "2") (pinfunction "A_2") (pintype "passive"))
    )
    (net (code "48") (name "Net-(TPSShrtGND-A)") (class "Default")
      (node (ref "R32") (pin "1") (pinfunction "1_1") (pintype "passive"))
      (node (ref "TPSShrtGND") (pin "2") (pinfunction "A_2") (pintype "passive"))
    )
    (net (code "49") (name "Net-(Trimmpoti 2-WIPER)") (class "Default")
      (node (ref "R10") (pin "2") (pinfunction "2_2") (pintype "passive"))
      (node (ref "Trimmpoti 2") (pin "2") (pinfunction "WIPER_2") (pintype "passive"))
      (node (ref "U4") (pin "4") (pinfunction "-IN_B_4") (pintype "input"))
    )
    (net (code "50") (name "Net-(Trimmpoti-WIPER)") (class "Default")
      (node (ref "R3") (pin "2") (pinfunction "2_2") (pintype "passive"))
      (node (ref "Trimmpoti") (pin "2") (pinfunction "WIPER_2") (pintype "passive"))
      (node (ref "U1") (pin "4") (pinfunction "-IN_B_4") (pintype "input"))
    )
    (net (code "51") (name "Net-(U1A-+IN_A)") (class "Default")
      (node (ref "R1") (pin "1") (pinfunction "1_1") (pintype "passive"))
      (node (ref "R2") (pin "2") (pinfunction "2_2") (pintype "passive"))
      (node (ref "R6") (pin "1") (pinfunction "1_1") (pintype "passive"))
      (node (ref "U1") (pin "1") (pinfunction "+IN_A_1") (pintype "input"))
    )
    (net (code "52") (name "Net-(U1B-+IN_B)") (class "Default")
      (node (ref "R4") (pin "2") (pinfunction "2_2") (pintype "passive"))
      (node (ref "R5") (pin "1") (pinfunction "1_1") (pintype "passive"))
      (node (ref "U1") (pin "3") (pinfunction "+IN_B_3") (pintype "input"))
    )
    (net (code "53") (name "Net-(U4A-+IN_A)") (class "Default")
      (node (ref "R7") (pin "1") (pinfunction "1_1") (pintype "passive"))
      (node (ref "R8") (pin "2") (pinfunction "2_2") (pintype "passive"))
      (node (ref "R9") (pin "1") (pinfunction "1_1") (pintype "passive"))
      (node (ref "U4") (pin "1") (pinfunction "+IN_A_1") (pintype "input"))
    )
    (net (code "54") (name "Net-(U4B-+IN_B)") (class "Default")
      (node (ref "R11") (pin "2") (pinfunction "2_2") (pintype "passive"))
      (node (ref "R12") (pin "1") (pinfunction "1_1") (pintype "passive"))
      (node (ref "U4") (pin "3") (pinfunction "+IN_B_3") (pintype "input"))
    )
    (net (code "55") (name "Net-(U8A-+IN_A)") (class "Default")
      (node (ref "R26") (pin "2") (pinfunction "2_2") (pintype "passive"))
      (node (ref "R27") (pin "1") (pinfunction "1_1") (pintype "passive"))
      (node (ref "U8") (pin "1") (pinfunction "+IN_A_1") (pintype "input"))
    )
    (net (code "56") (name "Net-(U8A--IN_A)") (class "Default")
      (node (ref "R24") (pin "1") (pinfunction "1_1") (pintype "passive"))
      (node (ref "R25") (pin "2") (pinfunction "2_2") (pintype "passive"))
      (node (ref "U8") (pin "8") (pinfunction "-IN_A_8") (pintype "input"))
    )
    (net (code "57") (name "Net-(U8B-+IN_B)") (class "Default")
      (node (ref "R30") (pin "2") (pinfunction "2_2") (pintype "passive"))
      (node (ref "R31") (pin "1") (pinfunction "1_1") (pintype "passive"))
      (node (ref "U8") (pin "3") (pinfunction "+IN_B_3") (pintype "input"))
    )
    (net (code "58") (name "Net-(U8B--IN_B)") (class "Default")
      (node (ref "R28") (pin "1") (pinfunction "1_1") (pintype "passive"))
      (node (ref "R29") (pin "2") (pinfunction "2_2") (pintype "passive"))
      (node (ref "U8") (pin "4") (pinfunction "-IN_B_4") (pintype "input"))
    )
    (net (code "59") (name "unconnected-(OP1-NC-Pad1)") (class "Default")
      (node (ref "OP1") (pin "1") (pinfunction "NC_1") (pintype "input"))
    )
    (net (code "60") (name "unconnected-(OP1-NC-Pad5)") (class "Default")
      (node (ref "OP1") (pin "5") (pinfunction "NC_5") (pintype "input"))
    )
    (net (code "61") (name "unconnected-(OP1-NC-Pad8)") (class "Default")
      (node (ref "OP1") (pin "8") (pinfunction "NC_8") (pintype "input"))
    )
    (net (code "62") (name "unconnected-(OP2-NC-Pad1)") (class "Default")
      (node (ref "OP2") (pin "1") (pinfunction "NC_1") (pintype "input"))
    )
    (net (code "63") (name "unconnected-(OP2-NC-Pad5)") (class "Default")
      (node (ref "OP2") (pin "5") (pinfunction "NC_5") (pintype "input"))
    )
    (net (code "64") (name "unconnected-(OP2-NC-Pad8)") (class "Default")
      (node (ref "OP2") (pin "8") (pinfunction "NC_8") (pintype "input"))
    )
    (net (code "65") (name "unconnected-(Trimmpoti 2-CW-Pad3)") (class "Default")
      (node (ref "Trimmpoti 2") (pin "3") (pinfunction "CW_3") (pintype "passive"))
    )
    (net (code "66") (name "unconnected-(Trimmpoti-CW-Pad3)") (class "Default")
      (node (ref "Trimmpoti") (pin "3") (pinfunction "CW_3") (pintype "passive"))
    )
  )
)
